# CLOCK.net
KiCad netlist of a schematic drawn in Altium Designer
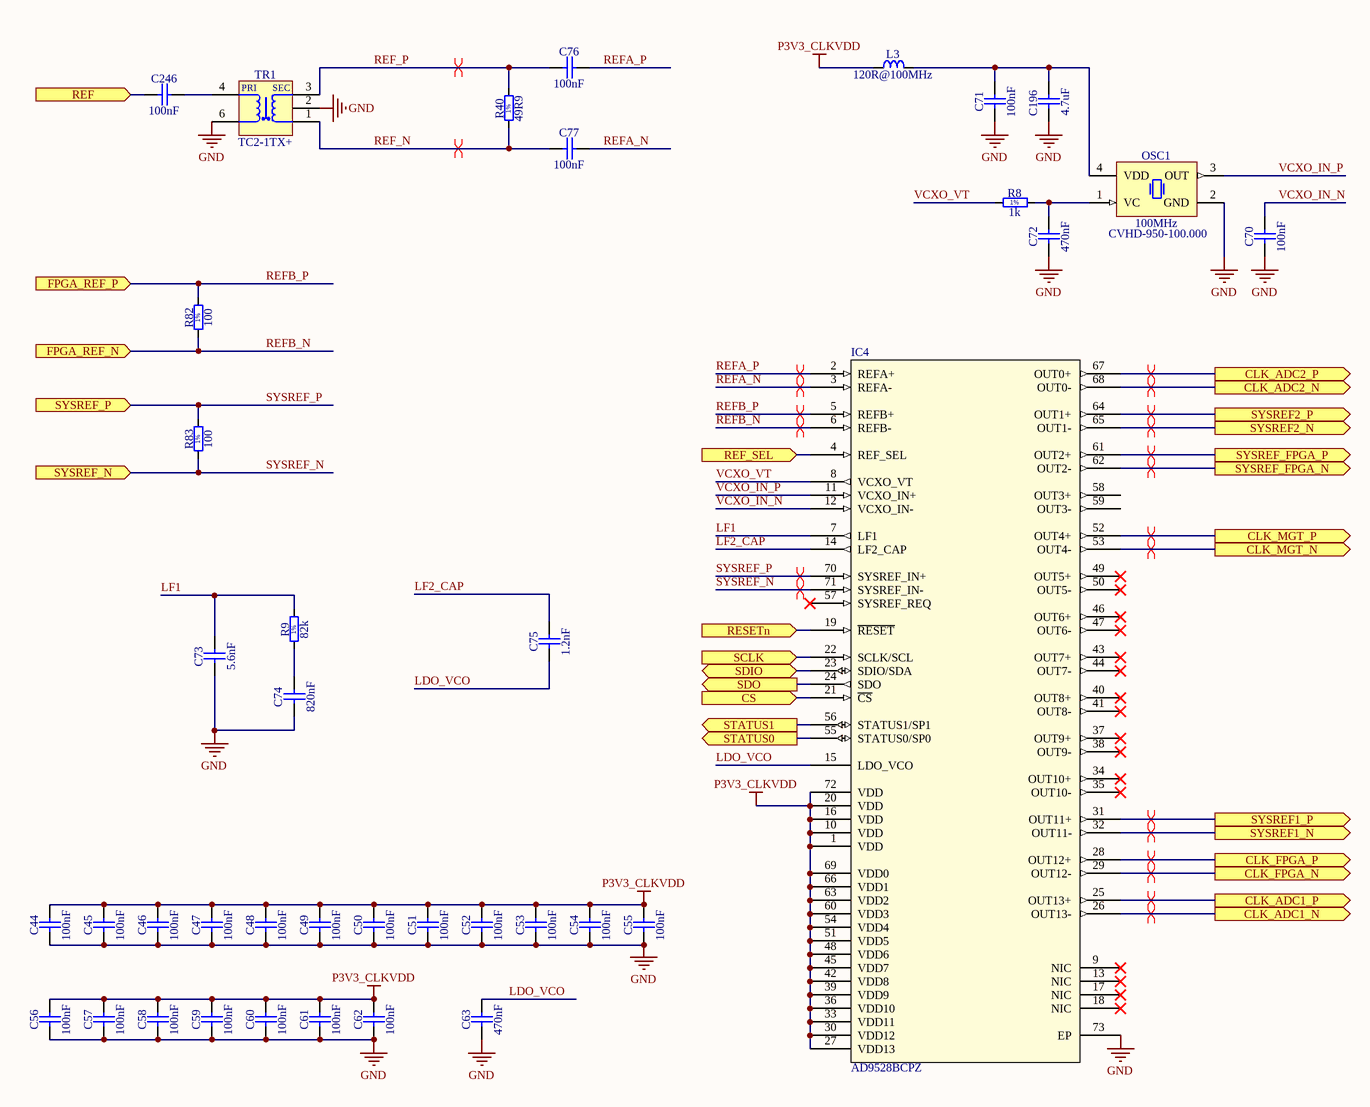
[diagram p0: CLOCK.SchDoc]

(export (version "E")
  (design (tool "Eeschema 10.0.6"))
  (components
    (comp (ref "C44")
      (value "100nF")
      (footprint "CAPC0603X33N")
      (description "Non-polarised capacitor")
      (fields
        (field (name "TOLERANCE") "±10%")
        (field (name "PART NUMBER") "CC0201_100NF_6.3V_10%_X5R")
        (field (name "AUTHOR") "CERN DEM JLC")
      )
      (libsource (lib "Capacitors") (part "Capacitor - non polarized"))
    )
    (comp (ref "C45")
      (value "100nF")
      (footprint "CAPC0603X33N")
      (description "Non-polarised capacitor")
      (fields
        (field (name "TOLERANCE") "±10%")
        (field (name "PART NUMBER") "CC0201_100NF_6.3V_10%_X5R")
        (field (name "AUTHOR") "CERN DEM JLC")
      )
      (libsource (lib "Capacitors") (part "Capacitor - non polarized"))
    )
    (comp (ref "C46")
      (value "100nF")
      (footprint "CAPC0603X33N")
      (description "Non-polarised capacitor")
      (fields
        (field (name "TOLERANCE") "±10%")
        (field (name "PART NUMBER") "CC0201_100NF_6.3V_10%_X5R")
        (field (name "AUTHOR") "CERN DEM JLC")
      )
      (libsource (lib "Capacitors") (part "Capacitor - non polarized"))
    )
    (comp (ref "C47")
      (value "100nF")
      (footprint "CAPC0603X33N")
      (description "Non-polarised capacitor")
      (fields
        (field (name "TOLERANCE") "±10%")
        (field (name "PART NUMBER") "CC0201_100NF_6.3V_10%_X5R")
        (field (name "AUTHOR") "CERN DEM JLC")
      )
      (libsource (lib "Capacitors") (part "Capacitor - non polarized"))
    )
    (comp (ref "C48")
      (value "100nF")
      (footprint "CAPC0603X33N")
      (description "Non-polarised capacitor")
      (fields
        (field (name "TOLERANCE") "±10%")
        (field (name "PART NUMBER") "CC0201_100NF_6.3V_10%_X5R")
        (field (name "AUTHOR") "CERN DEM JLC")
      )
      (libsource (lib "Capacitors") (part "Capacitor - non polarized"))
    )
    (comp (ref "C49")
      (value "100nF")
      (footprint "CAPC0603X33N")
      (description "Non-polarised capacitor")
      (fields
        (field (name "TOLERANCE") "±10%")
        (field (name "PART NUMBER") "CC0201_100NF_6.3V_10%_X5R")
        (field (name "AUTHOR") "CERN DEM JLC")
      )
      (libsource (lib "Capacitors") (part "Capacitor - non polarized"))
    )
    (comp (ref "C50")
      (value "100nF")
      (footprint "CAPC0603X33N")
      (description "Non-polarised capacitor")
      (fields
        (field (name "TOLERANCE") "±10%")
        (field (name "PART NUMBER") "CC0201_100NF_6.3V_10%_X5R")
        (field (name "AUTHOR") "CERN DEM JLC")
      )
      (libsource (lib "Capacitors") (part "Capacitor - non polarized"))
    )
    (comp (ref "C51")
      (value "100nF")
      (footprint "CAPC0603X33N")
      (description "Non-polarised capacitor")
      (fields
        (field (name "TOLERANCE") "±10%")
        (field (name "PART NUMBER") "CC0201_100NF_6.3V_10%_X5R")
        (field (name "AUTHOR") "CERN DEM JLC")
      )
      (libsource (lib "Capacitors") (part "Capacitor - non polarized"))
    )
    (comp (ref "C52")
      (value "100nF")
      (footprint "CAPC0603X33N")
      (description "Non-polarised capacitor")
      (fields
        (field (name "TOLERANCE") "±10%")
        (field (name "PART NUMBER") "CC0201_100NF_6.3V_10%_X5R")
        (field (name "AUTHOR") "CERN DEM JLC")
      )
      (libsource (lib "Capacitors") (part "Capacitor - non polarized"))
    )
    (comp (ref "C53")
      (value "100nF")
      (footprint "CAPC0603X33N")
      (description "Non-polarised capacitor")
      (fields
        (field (name "TOLERANCE") "±10%")
        (field (name "PART NUMBER") "CC0201_100NF_6.3V_10%_X5R")
        (field (name "AUTHOR") "CERN DEM JLC")
      )
      (libsource (lib "Capacitors") (part "Capacitor - non polarized"))
    )
    (comp (ref "C54")
      (value "100nF")
      (footprint "CAPC0603X33N")
      (description "Non-polarised capacitor")
      (fields
        (field (name "TOLERANCE") "±10%")
        (field (name "PART NUMBER") "CC0201_100NF_6.3V_10%_X5R")
        (field (name "AUTHOR") "CERN DEM JLC")
      )
      (libsource (lib "Capacitors") (part "Capacitor - non polarized"))
    )
    (comp (ref "C55")
      (value "100nF")
      (footprint "CAPC0603X33N")
      (description "Non-polarised capacitor")
      (fields
        (field (name "TOLERANCE") "±10%")
        (field (name "PART NUMBER") "CC0201_100NF_6.3V_10%_X5R")
        (field (name "AUTHOR") "CERN DEM JLC")
      )
      (libsource (lib "Capacitors") (part "Capacitor - non polarized"))
    )
    (comp (ref "C56")
      (value "100nF")
      (footprint "CAPC0603X33N")
      (description "Non-polarised capacitor")
      (fields
        (field (name "TOLERANCE") "±10%")
        (field (name "PART NUMBER") "CC0201_100NF_6.3V_10%_X5R")
        (field (name "AUTHOR") "CERN DEM JLC")
      )
      (libsource (lib "Capacitors") (part "Capacitor - non polarized"))
    )
    (comp (ref "C57")
      (value "100nF")
      (footprint "CAPC0603X33N")
      (description "Non-polarised capacitor")
      (fields
        (field (name "TOLERANCE") "±10%")
        (field (name "PART NUMBER") "CC0201_100NF_6.3V_10%_X5R")
        (field (name "AUTHOR") "CERN DEM JLC")
      )
      (libsource (lib "Capacitors") (part "Capacitor - non polarized"))
    )
    (comp (ref "C58")
      (value "100nF")
      (footprint "CAPC0603X33N")
      (description "Non-polarised capacitor")
      (fields
        (field (name "TOLERANCE") "±10%")
        (field (name "PART NUMBER") "CC0201_100NF_6.3V_10%_X5R")
        (field (name "AUTHOR") "CERN DEM JLC")
      )
      (libsource (lib "Capacitors") (part "Capacitor - non polarized"))
    )
    (comp (ref "C59")
      (value "100nF")
      (footprint "CAPC0603X33N")
      (description "Non-polarised capacitor")
      (fields
        (field (name "TOLERANCE") "±10%")
        (field (name "PART NUMBER") "CC0201_100NF_6.3V_10%_X5R")
        (field (name "AUTHOR") "CERN DEM JLC")
      )
      (libsource (lib "Capacitors") (part "Capacitor - non polarized"))
    )
    (comp (ref "C60")
      (value "100nF")
      (footprint "CAPC0603X33N")
      (description "Non-polarised capacitor")
      (fields
        (field (name "TOLERANCE") "±10%")
        (field (name "PART NUMBER") "CC0201_100NF_6.3V_10%_X5R")
        (field (name "AUTHOR") "CERN DEM JLC")
      )
      (libsource (lib "Capacitors") (part "Capacitor - non polarized"))
    )
    (comp (ref "C61")
      (value "100nF")
      (footprint "CAPC0603X33N")
      (description "Non-polarised capacitor")
      (fields
        (field (name "TOLERANCE") "±10%")
        (field (name "PART NUMBER") "CC0201_100NF_6.3V_10%_X5R")
        (field (name "AUTHOR") "CERN DEM JLC")
      )
      (libsource (lib "Capacitors") (part "Capacitor - non polarized"))
    )
    (comp (ref "C62")
      (value "100nF")
      (footprint "CAPC0603X33N")
      (description "Non-polarised capacitor")
      (fields
        (field (name "TOLERANCE") "±10%")
        (field (name "PART NUMBER") "CC0201_100NF_6.3V_10%_X5R")
        (field (name "AUTHOR") "CERN DEM JLC")
      )
      (libsource (lib "Capacitors") (part "Capacitor - non polarized"))
    )
    (comp (ref "C63")
      (value "470nF")
      (footprint "CAPC1005X55N")
      (description "Non-polarised capacitor")
      (fields
        (field (name "TOLERANCE") "±10%")
        (field (name "PART NUMBER") "CC0402_470NF_6.3V_10%_X5R")
        (field (name "AUTHOR") "CERN DEM JLC")
      )
      (libsource (lib "Capacitors") (part "Capacitor - non polarized"))
    )
    (comp (ref "C70")
      (value "100nF")
      (footprint "CAPC0603X33N")
      (description "Non-polarised capacitor")
      (fields
        (field (name "TOLERANCE") "±10%")
        (field (name "PART NUMBER") "CC0201_100NF_6.3V_10%_X5R")
        (field (name "AUTHOR") "CERN DEM JLC")
      )
      (libsource (lib "Capacitors") (part "Capacitor - non polarized"))
    )
    (comp (ref "C71")
      (value "100nF")
      (footprint "CAPC0603X33N")
      (description "Non-polarised capacitor")
      (fields
        (field (name "TOLERANCE") "±10%")
        (field (name "PART NUMBER") "CC0201_100NF_6.3V_10%_X5R")
        (field (name "AUTHOR") "CERN DEM JLC")
      )
      (libsource (lib "Capacitors") (part "Capacitor - non polarized"))
    )
    (comp (ref "C72")
      (value "470nF")
      (footprint "CAPC1005X55N")
      (description "Non-polarised capacitor")
      (fields
        (field (name "TOLERANCE") "±10%")
        (field (name "PART NUMBER") "CC0402_470NF_6.3V_10%_X5R")
        (field (name "AUTHOR") "CERN DEM JLC")
      )
      (libsource (lib "Capacitors") (part "Capacitor - non polarized"))
    )
    (comp (ref "C73")
      (value "5.6nF")
      (footprint "CAPC2012X88N")
      (description "Non-polarised capacitor")
      (fields
        (field (name "PART NUMBER") "CC0805_5.6NF_50V_5%_C0G")
        (field (name "VOLTAGE") "50V")
        (field (name "AUTHOR") "*")
      )
      (libsource (lib "FMC_ADC") (part "CC0805_5.6NF_50V_5%_C0G"))
    )
    (comp (ref "C74")
      (value "820nF")
      (footprint "CAPC3216X130N")
      (description "Non-polarised capacitor")
      (fields (field (name "PART NUMBER") "CC1206_820NF_25V_10%_X7R") (field (name "VOLTAGE") "25V"))
      (libsource (lib "FMC_ADC") (part "CC1206_820NF_25V_10%_X7R"))
    )
    (comp (ref "C75")
      (value "1.2nF")
      (footprint "CAPC1608X80N")
      (description "Non-polarised capacitor")
      (fields
        (field (name "TOLERANCE") "±5%")
        (field (name "PART NUMBER") "CC0603_1.2NF_50V_5%_C0G")
        (field (name "AUTHOR") "*")
      )
      (libsource (lib "FMC_ADC") (part "CC0603_1.2NF_50V_5%_C0G"))
    )
    (comp (ref "C76")
      (value "100nF")
      (footprint "CAPC1005X55N")
      (description "Non-polarised capacitor")
      (fields
        (field (name "TOLERANCE") "±10%")
        (field (name "PART NUMBER") "CC0402_100NF_16V_10%_X5R")
        (field (name "AUTHOR") "CERN DEM JLC")
      )
      (libsource (lib "Capacitors") (part "Capacitor - non polarized"))
    )
    (comp (ref "C77")
      (value "100nF")
      (footprint "CAPC1005X55N")
      (description "Non-polarised capacitor")
      (fields
        (field (name "TOLERANCE") "±10%")
        (field (name "PART NUMBER") "CC0402_100NF_16V_10%_X5R")
        (field (name "AUTHOR") "CERN DEM JLC")
      )
      (libsource (lib "Capacitors") (part "Capacitor - non polarized"))
    )
    (comp (ref "C196")
      (value "4.7uF")
      (footprint "CAPC1608X87N")
      (description "Non-polarised capacitor")
      (fields
        (field (name "PART NUMBER") "CC0603_4.7UF_6.3V_10%_X5R")
        (field (name "VOLTAGE") "6.3V")
        (field (name "AUTHOR") "CERN DEM JLC")
      )
      (libsource (lib "Capacitors") (part "Capacitor - non polarized"))
    )
    (comp (ref "C246")
      (value "100nF")
      (footprint "CAPC0603X33N")
      (description "Non-polarised capacitor")
      (fields
        (field (name "PART NUMBER") "CC0201_100NF_6.3V_10%_X5R")
        (field (name "VOLTAGE") "6.3V")
        (field (name "AUTHOR") "CERN DEM JLC")
      )
      (libsource (lib "Capacitors") (part "Capacitor - non polarized"))
    )
    (comp (ref "IC4")
      (value "AD9528BCPZ")
      (footprint "CP_72_6")
      (description "JESD204B Clock Generator with 14 LVDS/HSTL Outputs")
      (fields (field (name "MANUFACTURER") "Analog Devices"))
      (libsource (lib "FMC_ADC") (part "AD9528BCPZ"))
    )
    (comp (ref "L3")
      (value "120R@100MHz")
      (footprint "INDC1608X65N")
      (description "Inductor")
      (fields
        (field (name "PART NUMBER") "IND0603_MURATA_BLM18SG121TN1D")
        (field (name "POWER") "3A")
        (field (name "AUTHOR") "CERN DEM JLC")
      )
      (libsource (lib "Inductors & Transformers") (part "Inductor"))
    )
    (comp (ref "OSC1")
      (value "100MHz")
      (footprint "OSC_CRYSTEK_CVHD-950")
      (description "Oscillator 4 pins 1=VC 2=GND 3=OUT 4=VDD")
      (fields
        (field (name "PART NUMBER") "OSC_125MHZ_CRYSTEK_CVHD-950-100.000")
        (field (name "MANUFACTURER") "CRYSTEK CRYSTAL")
        (field (name "MANUFACTURER PART NUMBER") "CVHD-950-100.000")
        (field (name "AUTHOR") "CERN DEM JLC")
      )
      (libsource (lib "ICs And Semiconductors") (part "Oscillator 1VC 2GND 3OUT 4VDD"))
    )
    (comp (ref "R8")
      (value "1k")
      (footprint "RESC1005X40N")
      (description "Resistor - 1%")
      (fields
        (field (name "TOLERANCE") "±1%")
        (field (name "POWER") "0.0625W")
        (field (name "AUTHOR") "CERN DEM JLC")
      )
      (libsource (lib "Resistors") (part "Resistor - 1%"))
    )
    (comp (ref "R9")
      (value "82k")
      (footprint "RESC1005X40N")
      (description "Resistor - 1%")
      (fields
        (field (name "TOLERANCE") "±1%")
        (field (name "POWER") "0.0625W")
        (field (name "AUTHOR") "CERN DEM JLC")
      )
      (libsource (lib "Resistors") (part "Resistor - 1%"))
    )
    (comp (ref "R40")
      (value "49R9")
      (footprint "RESC1005X40N")
      (description "Resistor - 1%")
      (fields
        (field (name "PART NUMBER") "R0402_49R9_1%_0.0625W_100PPM")
        (field (name "POWER") "0.0625W")
        (field (name "AUTHOR") "CERN DEM JLC")
      )
      (libsource (lib "Resistors") (part "Resistor - 1%"))
    )
    (comp (ref "R82")
      (value "100")
      (footprint "RESC1005X40N")
      (description "Resistor - 1%")
      (fields
        (field (name "PART NUMBER") "R0402_100R_1%_0.0625W_100PPM")
        (field (name "POWER") "0.0625W")
        (field (name "AUTHOR") "CERN DEM JLC")
      )
      (libsource (lib "Resistors") (part "Resistor - 1%"))
    )
    (comp (ref "R83")
      (value "100")
      (footprint "RESC1005X40N")
      (description "Resistor - 1%")
      (fields
        (field (name "PART NUMBER") "R0402_100R_1%_0.0625W_100PPM")
        (field (name "POWER") "0.0625W")
        (field (name "AUTHOR") "CERN DEM JLC")
      )
      (libsource (lib "Resistors") (part "Resistor - 1%"))
    )
    (comp (ref "TR1")
      (value "TC2-1TX+")
      (footprint "XFMR_MINI-CIRCUITS_AT1521")
      (description "50 Ohm 3 to 300MHz RF Transformer")
      (fields (field (name "MANUFACTURER") "MINI-CIRCUITS"))
      (libsource (lib "FMC_ADC") (part "XFMR_MINI-CIRCUITS_TC2-1TX+"))
    )
  )
  (nets
    (net (code "1") (name "/CLK_ADC1_N") (class "Default")
      (node (ref "IC4") (pin "26") (pinfunction "OUT13-_26") (pintype "output"))
    )
    (net (code "2") (name "/CLK_ADC1_P") (class "Default")
      (node (ref "IC4") (pin "25") (pinfunction "OUT13+_25") (pintype "output"))
    )
    (net (code "3") (name "/CLK_ADC2_N") (class "Default")
      (node (ref "IC4") (pin "68") (pinfunction "OUT0-_68") (pintype "output"))
    )
    (net (code "4") (name "/CLK_ADC2_P") (class "Default")
      (node (ref "IC4") (pin "67") (pinfunction "OUT0+_67") (pintype "output"))
    )
    (net (code "5") (name "/CLK_FPGA_N") (class "Default")
      (node (ref "IC4") (pin "29") (pinfunction "OUT12-_29") (pintype "output"))
    )
    (net (code "6") (name "/CLK_FPGA_P") (class "Default")
      (node (ref "IC4") (pin "28") (pinfunction "OUT12+_28") (pintype "output"))
    )
    (net (code "7") (name "/CLK_MGT_N") (class "Default")
      (node (ref "IC4") (pin "53") (pinfunction "OUT4-_53") (pintype "output"))
    )
    (net (code "8") (name "/CLK_MGT_P") (class "Default")
      (node (ref "IC4") (pin "52") (pinfunction "OUT4+_52") (pintype "output"))
    )
    (net (code "9") (name "/CS") (class "Default")
      (node (ref "IC4") (pin "21") (pinfunction "~{CS}_21") (pintype "input"))
    )
    (net (code "10") (name "/LDO_VCO") (class "Default")
      (node (ref "C63") (pin "2") (pinfunction "2_2") (pintype "passive"))
      (node (ref "C75") (pin "1") (pinfunction "1_1") (pintype "passive"))
      (node (ref "IC4") (pin "15") (pinfunction "LDO_VCO_15") (pintype "power_in"))
    )
    (net (code "11") (name "/LF1") (class "Default")
      (node (ref "C73") (pin "2") (pinfunction "2_2") (pintype "passive"))
      (node (ref "IC4") (pin "7") (pinfunction "LF1_7") (pintype "output"))
      (node (ref "R9") (pin "2") (pinfunction "2_2") (pintype "passive"))
    )
    (net (code "12") (name "/LF2_CAP") (class "Default")
      (node (ref "C75") (pin "2") (pinfunction "2_2") (pintype "passive"))
      (node (ref "IC4") (pin "14") (pinfunction "LF2_CAP_14") (pintype "output"))
    )
    (net (code "13") (name "/REF") (class "Default")
      (node (ref "C246") (pin "1") (pinfunction "1_1") (pintype "passive"))
    )
    (net (code "14") (name "/REFA_N") (class "Default")
      (node (ref "C77") (pin "2") (pinfunction "2_2") (pintype "passive"))
      (node (ref "IC4") (pin "3") (pinfunction "REFA-_3") (pintype "input"))
    )
    (net (code "15") (name "/REFA_P") (class "Default")
      (node (ref "C76") (pin "2") (pinfunction "2_2") (pintype "passive"))
      (node (ref "IC4") (pin "2") (pinfunction "REFA+_2") (pintype "input"))
    )
    (net (code "16") (name "/REFB_N") (class "Default")
      (node (ref "IC4") (pin "6") (pinfunction "REFB-_6") (pintype "input"))
      (node (ref "R82") (pin "1") (pinfunction "1_1") (pintype "passive"))
    )
    (net (code "17") (name "/REFB_P") (class "Default")
      (node (ref "IC4") (pin "5") (pinfunction "REFB+_5") (pintype "input"))
      (node (ref "R82") (pin "2") (pinfunction "2_2") (pintype "passive"))
    )
    (net (code "18") (name "/REF_N") (class "Default")
      (node (ref "C77") (pin "1") (pinfunction "1_1") (pintype "passive"))
      (node (ref "R40") (pin "1") (pinfunction "1_1") (pintype "passive"))
      (node (ref "TR1") (pin "1") (pinfunction "SDOT_1") (pintype "passive"))
    )
    (net (code "19") (name "/REF_P") (class "Default")
      (node (ref "C76") (pin "1") (pinfunction "1_1") (pintype "passive"))
      (node (ref "R40") (pin "2") (pinfunction "2_2") (pintype "passive"))
      (node (ref "TR1") (pin "3") (pinfunction "S_3") (pintype "passive"))
    )
    (net (code "20") (name "/REF_SEL") (class "Default")
      (node (ref "IC4") (pin "4") (pinfunction "REF_SEL_4") (pintype "input"))
    )
    (net (code "21") (name "/RESETn") (class "Default")
      (node (ref "IC4") (pin "19") (pinfunction "~{RESET}_19") (pintype "input"))
    )
    (net (code "22") (name "/SCLK") (class "Default")
      (node (ref "IC4") (pin "22") (pinfunction "SCLK/SCL_22") (pintype "input"))
    )
    (net (code "23") (name "/SDIO") (class "Default")
      (node (ref "IC4") (pin "23") (pinfunction "SDIO/SDA_23") (pintype "bidirectional"))
    )
    (net (code "24") (name "/SDO") (class "Default")
      (node (ref "IC4") (pin "24") (pinfunction "SDO_24") (pintype "output"))
    )
    (net (code "25") (name "/STATUS0") (class "Default")
      (node (ref "IC4") (pin "55") (pinfunction "STATUS0/SP0_55") (pintype "bidirectional"))
    )
    (net (code "26") (name "/STATUS1") (class "Default")
      (node (ref "IC4") (pin "56") (pinfunction "STATUS1/SP1_56") (pintype "bidirectional"))
    )
    (net (code "27") (name "/SYSREF1_N") (class "Default")
      (node (ref "IC4") (pin "32") (pinfunction "OUT11-_32") (pintype "output"))
    )
    (net (code "28") (name "/SYSREF1_P") (class "Default")
      (node (ref "IC4") (pin "31") (pinfunction "OUT11+_31") (pintype "output"))
    )
    (net (code "29") (name "/SYSREF2_N") (class "Default")
      (node (ref "IC4") (pin "65") (pinfunction "OUT1-_65") (pintype "output"))
    )
    (net (code "30") (name "/SYSREF2_P") (class "Default")
      (node (ref "IC4") (pin "64") (pinfunction "OUT1+_64") (pintype "output"))
    )
    (net (code "31") (name "/SYSREF_FPGA_N") (class "Default")
      (node (ref "IC4") (pin "62") (pinfunction "OUT2-_62") (pintype "output"))
    )
    (net (code "32") (name "/SYSREF_FPGA_P") (class "Default")
      (node (ref "IC4") (pin "61") (pinfunction "OUT2+_61") (pintype "output"))
    )
    (net (code "33") (name "/SYSREF_N") (class "Default")
      (node (ref "IC4") (pin "71") (pinfunction "SYSREF_IN-_71") (pintype "input"))
      (node (ref "R83") (pin "1") (pinfunction "1_1") (pintype "passive"))
    )
    (net (code "34") (name "/SYSREF_P") (class "Default")
      (node (ref "IC4") (pin "70") (pinfunction "SYSREF_IN+_70") (pintype "input"))
      (node (ref "R83") (pin "2") (pinfunction "2_2") (pintype "passive"))
    )
    (net (code "35") (name "/VCXO_IN_N") (class "Default")
      (node (ref "C70") (pin "2") (pinfunction "2_2") (pintype "passive"))
      (node (ref "IC4") (pin "12") (pinfunction "VCXO_IN-_12") (pintype "input"))
    )
    (net (code "36") (name "/VCXO_IN_P") (class "Default")
      (node (ref "IC4") (pin "11") (pinfunction "VCXO_IN+_11") (pintype "input"))
      (node (ref "OSC1") (pin "3") (pinfunction "OUT_3") (pintype "output"))
    )
    (net (code "37") (name "/VCXO_VT") (class "Default")
      (node (ref "IC4") (pin "8") (pinfunction "VCXO_VT_8") (pintype "output"))
      (node (ref "R8") (pin "1") (pinfunction "1_1") (pintype "passive"))
    )
    (net (code "38") (name "GND") (class "Default")
      (node (ref "C196") (pin "1") (pinfunction "1_1") (pintype "passive"))
      (node (ref "C44") (pin "1") (pinfunction "1_1") (pintype "passive"))
      (node (ref "C45") (pin "1") (pinfunction "1_1") (pintype "passive"))
      (node (ref "C46") (pin "1") (pinfunction "1_1") (pintype "passive"))
      (node (ref "C47") (pin "1") (pinfunction "1_1") (pintype "passive"))
      (node (ref "C48") (pin "1") (pinfunction "1_1") (pintype "passive"))
      (node (ref "C49") (pin "1") (pinfunction "1_1") (pintype "passive"))
      (node (ref "C50") (pin "1") (pinfunction "1_1") (pintype "passive"))
      (node (ref "C51") (pin "1") (pinfunction "1_1") (pintype "passive"))
      (node (ref "C52") (pin "1") (pinfunction "1_1") (pintype "passive"))
      (node (ref "C53") (pin "1") (pinfunction "1_1") (pintype "passive"))
      (node (ref "C54") (pin "1") (pinfunction "1_1") (pintype "passive"))
      (node (ref "C55") (pin "1") (pinfunction "1_1") (pintype "passive"))
      (node (ref "C56") (pin "1") (pinfunction "1_1") (pintype "passive"))
      (node (ref "C57") (pin "1") (pinfunction "1_1") (pintype "passive"))
      (node (ref "C58") (pin "1") (pinfunction "1_1") (pintype "passive"))
      (node (ref "C59") (pin "1") (pinfunction "1_1") (pintype "passive"))
      (node (ref "C60") (pin "1") (pinfunction "1_1") (pintype "passive"))
      (node (ref "C61") (pin "1") (pinfunction "1_1") (pintype "passive"))
      (node (ref "C62") (pin "1") (pinfunction "1_1") (pintype "passive"))
      (node (ref "C63") (pin "1") (pinfunction "1_1") (pintype "passive"))
      (node (ref "C70") (pin "1") (pinfunction "1_1") (pintype "passive"))
      (node (ref "C71") (pin "1") (pinfunction "1_1") (pintype "passive"))
      (node (ref "C72") (pin "1") (pinfunction "1_1") (pintype "passive"))
      (node (ref "C73") (pin "1") (pinfunction "1_1") (pintype "passive"))
      (node (ref "C74") (pin "1") (pinfunction "1_1") (pintype "passive"))
      (node (ref "IC4") (pin "73") (pinfunction "EP_73") (pintype "power_in"))
      (node (ref "OSC1") (pin "2") (pinfunction "GND_2") (pintype "power_in"))
      (node (ref "TR1") (pin "2") (pinfunction "NU_2") (pintype "passive"))
      (node (ref "TR1") (pin "6") (pinfunction "PDOT_6") (pintype "passive"))
    )
    (net (code "39") (name "Net-(C74-Pad2)") (class "Default")
      (node (ref "C74") (pin "2") (pinfunction "2_2") (pintype "passive"))
      (node (ref "R9") (pin "1") (pinfunction "1_1") (pintype "passive"))
    )
    (net (code "40") (name "Net-(OSC1-VC)") (class "Default")
      (node (ref "C72") (pin "2") (pinfunction "2_2") (pintype "passive"))
      (node (ref "OSC1") (pin "1") (pinfunction "VC_1") (pintype "input"))
      (node (ref "R8") (pin "2") (pinfunction "2_2") (pintype "passive"))
    )
    (net (code "41") (name "Net-(OSC1-VDD)") (class "Default")
      (node (ref "C196") (pin "2") (pinfunction "2_2") (pintype "passive"))
      (node (ref "C71") (pin "2") (pinfunction "2_2") (pintype "passive"))
      (node (ref "L3") (pin "2") (pinfunction "2_2") (pintype "passive"))
      (node (ref "OSC1") (pin "4") (pinfunction "VDD_4") (pintype "power_in"))
    )
    (net (code "42") (name "Net-(TR1-P)") (class "Default")
      (node (ref "C246") (pin "2") (pinfunction "2_2") (pintype "passive"))
      (node (ref "TR1") (pin "4") (pinfunction "P_4") (pintype "passive"))
    )
    (net (code "43") (name "P3V3_CLKVDD") (class "Default")
      (node (ref "C44") (pin "2") (pinfunction "2_2") (pintype "passive"))
      (node (ref "C45") (pin "2") (pinfunction "2_2") (pintype "passive"))
      (node (ref "C46") (pin "2") (pinfunction "2_2") (pintype "passive"))
      (node (ref "C47") (pin "2") (pinfunction "2_2") (pintype "passive"))
      (node (ref "C48") (pin "2") (pinfunction "2_2") (pintype "passive"))
      (node (ref "C49") (pin "2") (pinfunction "2_2") (pintype "passive"))
      (node (ref "C50") (pin "2") (pinfunction "2_2") (pintype "passive"))
      (node (ref "C51") (pin "2") (pinfunction "2_2") (pintype "passive"))
      (node (ref "C52") (pin "2") (pinfunction "2_2") (pintype "passive"))
      (node (ref "C53") (pin "2") (pinfunction "2_2") (pintype "passive"))
      (node (ref "C54") (pin "2") (pinfunction "2_2") (pintype "passive"))
      (node (ref "C55") (pin "2") (pinfunction "2_2") (pintype "passive"))
      (node (ref "C56") (pin "2") (pinfunction "2_2") (pintype "passive"))
      (node (ref "C57") (pin "2") (pinfunction "2_2") (pintype "passive"))
      (node (ref "C58") (pin "2") (pinfunction "2_2") (pintype "passive"))
      (node (ref "C59") (pin "2") (pinfunction "2_2") (pintype "passive"))
      (node (ref "C60") (pin "2") (pinfunction "2_2") (pintype "passive"))
      (node (ref "C61") (pin "2") (pinfunction "2_2") (pintype "passive"))
      (node (ref "C62") (pin "2") (pinfunction "2_2") (pintype "passive"))
      (node (ref "IC4") (pin "1") (pinfunction "VDD_1") (pintype "power_in"))
      (node (ref "IC4") (pin "10") (pinfunction "VDD_10") (pintype "power_in"))
      (node (ref "IC4") (pin "16") (pinfunction "VDD_16") (pintype "power_in"))
      (node (ref "IC4") (pin "20") (pinfunction "VDD_20") (pintype "power_in"))
      (node (ref "IC4") (pin "27") (pinfunction "VDD13_27") (pintype "power_in"))
      (node (ref "IC4") (pin "30") (pinfunction "VDD12_30") (pintype "power_in"))
      (node (ref "IC4") (pin "33") (pinfunction "VDD11_33") (pintype "power_in"))
      (node (ref "IC4") (pin "36") (pinfunction "VDD10_36") (pintype "power_in"))
      (node (ref "IC4") (pin "39") (pinfunction "VDD9_39") (pintype "power_in"))
      (node (ref "IC4") (pin "42") (pinfunction "VDD8_42") (pintype "power_in"))
      (node (ref "IC4") (pin "45") (pinfunction "VDD7_45") (pintype "power_in"))
      (node (ref "IC4") (pin "48") (pinfunction "VDD6_48") (pintype "power_in"))
      (node (ref "IC4") (pin "51") (pinfunction "VDD5_51") (pintype "power_in"))
      (node (ref "IC4") (pin "54") (pinfunction "VDD4_54") (pintype "power_in"))
      (node (ref "IC4") (pin "60") (pinfunction "VDD3_60") (pintype "power_in"))
      (node (ref "IC4") (pin "63") (pinfunction "VDD2_63") (pintype "power_in"))
      (node (ref "IC4") (pin "66") (pinfunction "VDD1_66") (pintype "power_in"))
      (node (ref "IC4") (pin "69") (pinfunction "VDD0_69") (pintype "power_in"))
      (node (ref "IC4") (pin "72") (pinfunction "VDD_72") (pintype "power_in"))
      (node (ref "L3") (pin "1") (pinfunction "1_1") (pintype "passive"))
    )
    (net (code "44") (name "unconnected-(IC4-NIC-Pad9)") (class "Default")
      (node (ref "IC4") (pin "9") (pinfunction "NIC_9") (pintype "passive+no_connect"))
    )
    (net (code "45") (name "unconnected-(IC4-NIC-Pad13)") (class "Default")
      (node (ref "IC4") (pin "13") (pinfunction "NIC_13") (pintype "passive+no_connect"))
    )
    (net (code "46") (name "unconnected-(IC4-NIC-Pad17)") (class "Default")
      (node (ref "IC4") (pin "17") (pinfunction "NIC_17") (pintype "passive+no_connect"))
    )
    (net (code "47") (name "unconnected-(IC4-NIC-Pad18)") (class "Default")
      (node (ref "IC4") (pin "18") (pinfunction "NIC_18") (pintype "passive+no_connect"))
    )
    (net (code "48") (name "unconnected-(IC4-OUT3+-Pad58)") (class "Default")
      (node (ref "IC4") (pin "58") (pinfunction "OUT3+_58") (pintype "output"))
    )
    (net (code "49") (name "unconnected-(IC4-OUT3--Pad59)") (class "Default")
      (node (ref "IC4") (pin "59") (pinfunction "OUT3-_59") (pintype "output"))
    )
    (net (code "50") (name "unconnected-(IC4-OUT5+-Pad49)") (class "Default")
      (node (ref "IC4") (pin "49") (pinfunction "OUT5+_49") (pintype "output+no_connect"))
    )
    (net (code "51") (name "unconnected-(IC4-OUT5--Pad50)") (class "Default")
      (node (ref "IC4") (pin "50") (pinfunction "OUT5-_50") (pintype "output+no_connect"))
    )
    (net (code "52") (name "unconnected-(IC4-OUT6+-Pad46)") (class "Default")
      (node (ref "IC4") (pin "46") (pinfunction "OUT6+_46") (pintype "output+no_connect"))
    )
    (net (code "53") (name "unconnected-(IC4-OUT6--Pad47)") (class "Default")
      (node (ref "IC4") (pin "47") (pinfunction "OUT6-_47") (pintype "output+no_connect"))
    )
    (net (code "54") (name "unconnected-(IC4-OUT7+-Pad43)") (class "Default")
      (node (ref "IC4") (pin "43") (pinfunction "OUT7+_43") (pintype "output+no_connect"))
    )
    (net (code "55") (name "unconnected-(IC4-OUT7--Pad44)") (class "Default")
      (node (ref "IC4") (pin "44") (pinfunction "OUT7-_44") (pintype "output+no_connect"))
    )
    (net (code "56") (name "unconnected-(IC4-OUT8+-Pad40)") (class "Default")
      (node (ref "IC4") (pin "40") (pinfunction "OUT8+_40") (pintype "output+no_connect"))
    )
    (net (code "57") (name "unconnected-(IC4-OUT8--Pad41)") (class "Default")
      (node (ref "IC4") (pin "41") (pinfunction "OUT8-_41") (pintype "output+no_connect"))
    )
    (net (code "58") (name "unconnected-(IC4-OUT9+-Pad37)") (class "Default")
      (node (ref "IC4") (pin "37") (pinfunction "OUT9+_37") (pintype "output+no_connect"))
    )
    (net (code "59") (name "unconnected-(IC4-OUT9--Pad38)") (class "Default")
      (node (ref "IC4") (pin "38") (pinfunction "OUT9-_38") (pintype "output+no_connect"))
    )
    (net (code "60") (name "unconnected-(IC4-OUT10+-Pad34)") (class "Default")
      (node (ref "IC4") (pin "34") (pinfunction "OUT10+_34") (pintype "output+no_connect"))
    )
    (net (code "61") (name "unconnected-(IC4-OUT10--Pad35)") (class "Default")
      (node (ref "IC4") (pin "35") (pinfunction "OUT10-_35") (pintype "output+no_connect"))
    )
    (net (code "62") (name "unconnected-(IC4-SYSREF_REQ-Pad57)") (class "Default")
      (node (ref "IC4") (pin "57") (pinfunction "SYSREF_REQ_57") (pintype "input+no_connect"))
    )
  )
)
